# TopLevel.net
KiCad netlist of a schematic drawn in Altium Designer
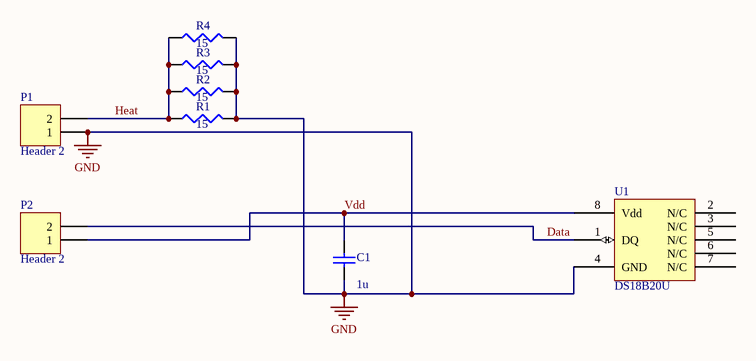
[diagram p0: TopLevel.SchDoc]

(export (version "E")
  (design (tool "Eeschema 10.0.6"))
  (components
    (comp (ref "C1")
      (value "1u")
      (footprint "C0805")
      (description "Capacitor")
      (libsource (lib "Suction") (part "Cap"))
    )
    (comp (ref "P1")
      (value "Header 2")
      (footprint "HDR1X2-SMT")
      (description "Header, 2-Pin")
      (fields (field (name "PUBLISHER") "Altium Limited"))
      (libsource (lib "Suction") (part "Header 2"))
    )
    (comp (ref "P2")
      (value "Header 2")
      (footprint "HDR1X2-SMT")
      (description "Header, 2-Pin")
      (fields (field (name "PUBLISHER") "Altium Limited"))
      (libsource (lib "Suction") (part "Header 2"))
    )
    (comp (ref "R1")
      (value "15")
      (footprint "Res-2512-6332")
      (description "Resistor")
      (libsource (lib "Suction") (part "Res3"))
    )
    (comp (ref "R2")
      (value "15")
      (footprint "Res-2512-6332")
      (description "Resistor")
      (libsource (lib "Suction") (part "Res3"))
    )
    (comp (ref "R3")
      (value "15")
      (footprint "Res-2512-6332")
      (description "Resistor")
      (libsource (lib "Suction") (part "Res3"))
    )
    (comp (ref "R4")
      (value "15")
      (footprint "Res-2512-6332")
      (description "Resistor")
      (libsource (lib "Suction") (part "Res3"))
    )
    (comp (ref "U1")
      (value "DS18B20U")
      (footprint "MSSOP-8")
      (description "Programmable Resolution 1-Wire Digital Thermometer")
      (libsource (lib "Suction") (part "DS18B20U"))
    )
  )
  (nets
    (net (code "1") (name "/Data") (class "Default")
      (node (ref "P2") (pin "2") (pinfunction "2_2") (pintype "passive"))
      (node (ref "U1") (pin "1") (pinfunction "DQ_1") (pintype "bidirectional"))
    )
    (net (code "2") (name "/Heat") (class "Default")
      (node (ref "P1") (pin "2") (pinfunction "2_2") (pintype "passive"))
      (node (ref "R1") (pin "1") (pinfunction "1_1") (pintype "passive"))
      (node (ref "R2") (pin "1") (pinfunction "1_1") (pintype "passive"))
      (node (ref "R3") (pin "1") (pinfunction "1_1") (pintype "passive"))
      (node (ref "R4") (pin "1") (pinfunction "1_1") (pintype "passive"))
    )
    (net (code "3") (name "/Vdd") (class "Default")
      (node (ref "C1") (pin "2") (pinfunction "2_2") (pintype "passive"))
      (node (ref "P2") (pin "1") (pinfunction "1_1") (pintype "passive"))
      (node (ref "U1") (pin "8") (pinfunction "Vdd_8") (pintype "power_in"))
    )
    (net (code "4") (name "GND") (class "Default")
      (node (ref "C1") (pin "1") (pinfunction "1_1") (pintype "passive"))
      (node (ref "P1") (pin "1") (pinfunction "1_1") (pintype "passive"))
      (node (ref "R1") (pin "2") (pinfunction "2_2") (pintype "passive"))
      (node (ref "R2") (pin "2") (pinfunction "2_2") (pintype "passive"))
      (node (ref "R3") (pin "2") (pinfunction "2_2") (pintype "passive"))
      (node (ref "R4") (pin "2") (pinfunction "2_2") (pintype "passive"))
      (node (ref "U1") (pin "4") (pinfunction "GND_4") (pintype "power_in"))
    )
    (net (code "5") (name "unconnected-(U1-N{slash}C-Pad2)") (class "Default")
      (node (ref "U1") (pin "2") (pinfunction "N/C_2") (pintype "passive"))
    )
    (net (code "6") (name "unconnected-(U1-N{slash}C-Pad3)") (class "Default")
      (node (ref "U1") (pin "3") (pinfunction "N/C_3") (pintype "passive"))
    )
    (net (code "7") (name "unconnected-(U1-N{slash}C-Pad5)") (class "Default")
      (node (ref "U1") (pin "5") (pinfunction "N/C_5") (pintype "passive"))
    )
    (net (code "8") (name "unconnected-(U1-N{slash}C-Pad6)") (class "Default")
      (node (ref "U1") (pin "6") (pinfunction "N/C_6") (pintype "passive"))
    )
    (net (code "9") (name "unconnected-(U1-N{slash}C-Pad7)") (class "Default")
      (node (ref "U1") (pin "7") (pinfunction "N/C_7") (pintype "passive"))
    )
  )
)
